# display.net
KiCad netlist of a schematic drawn in EAGLE
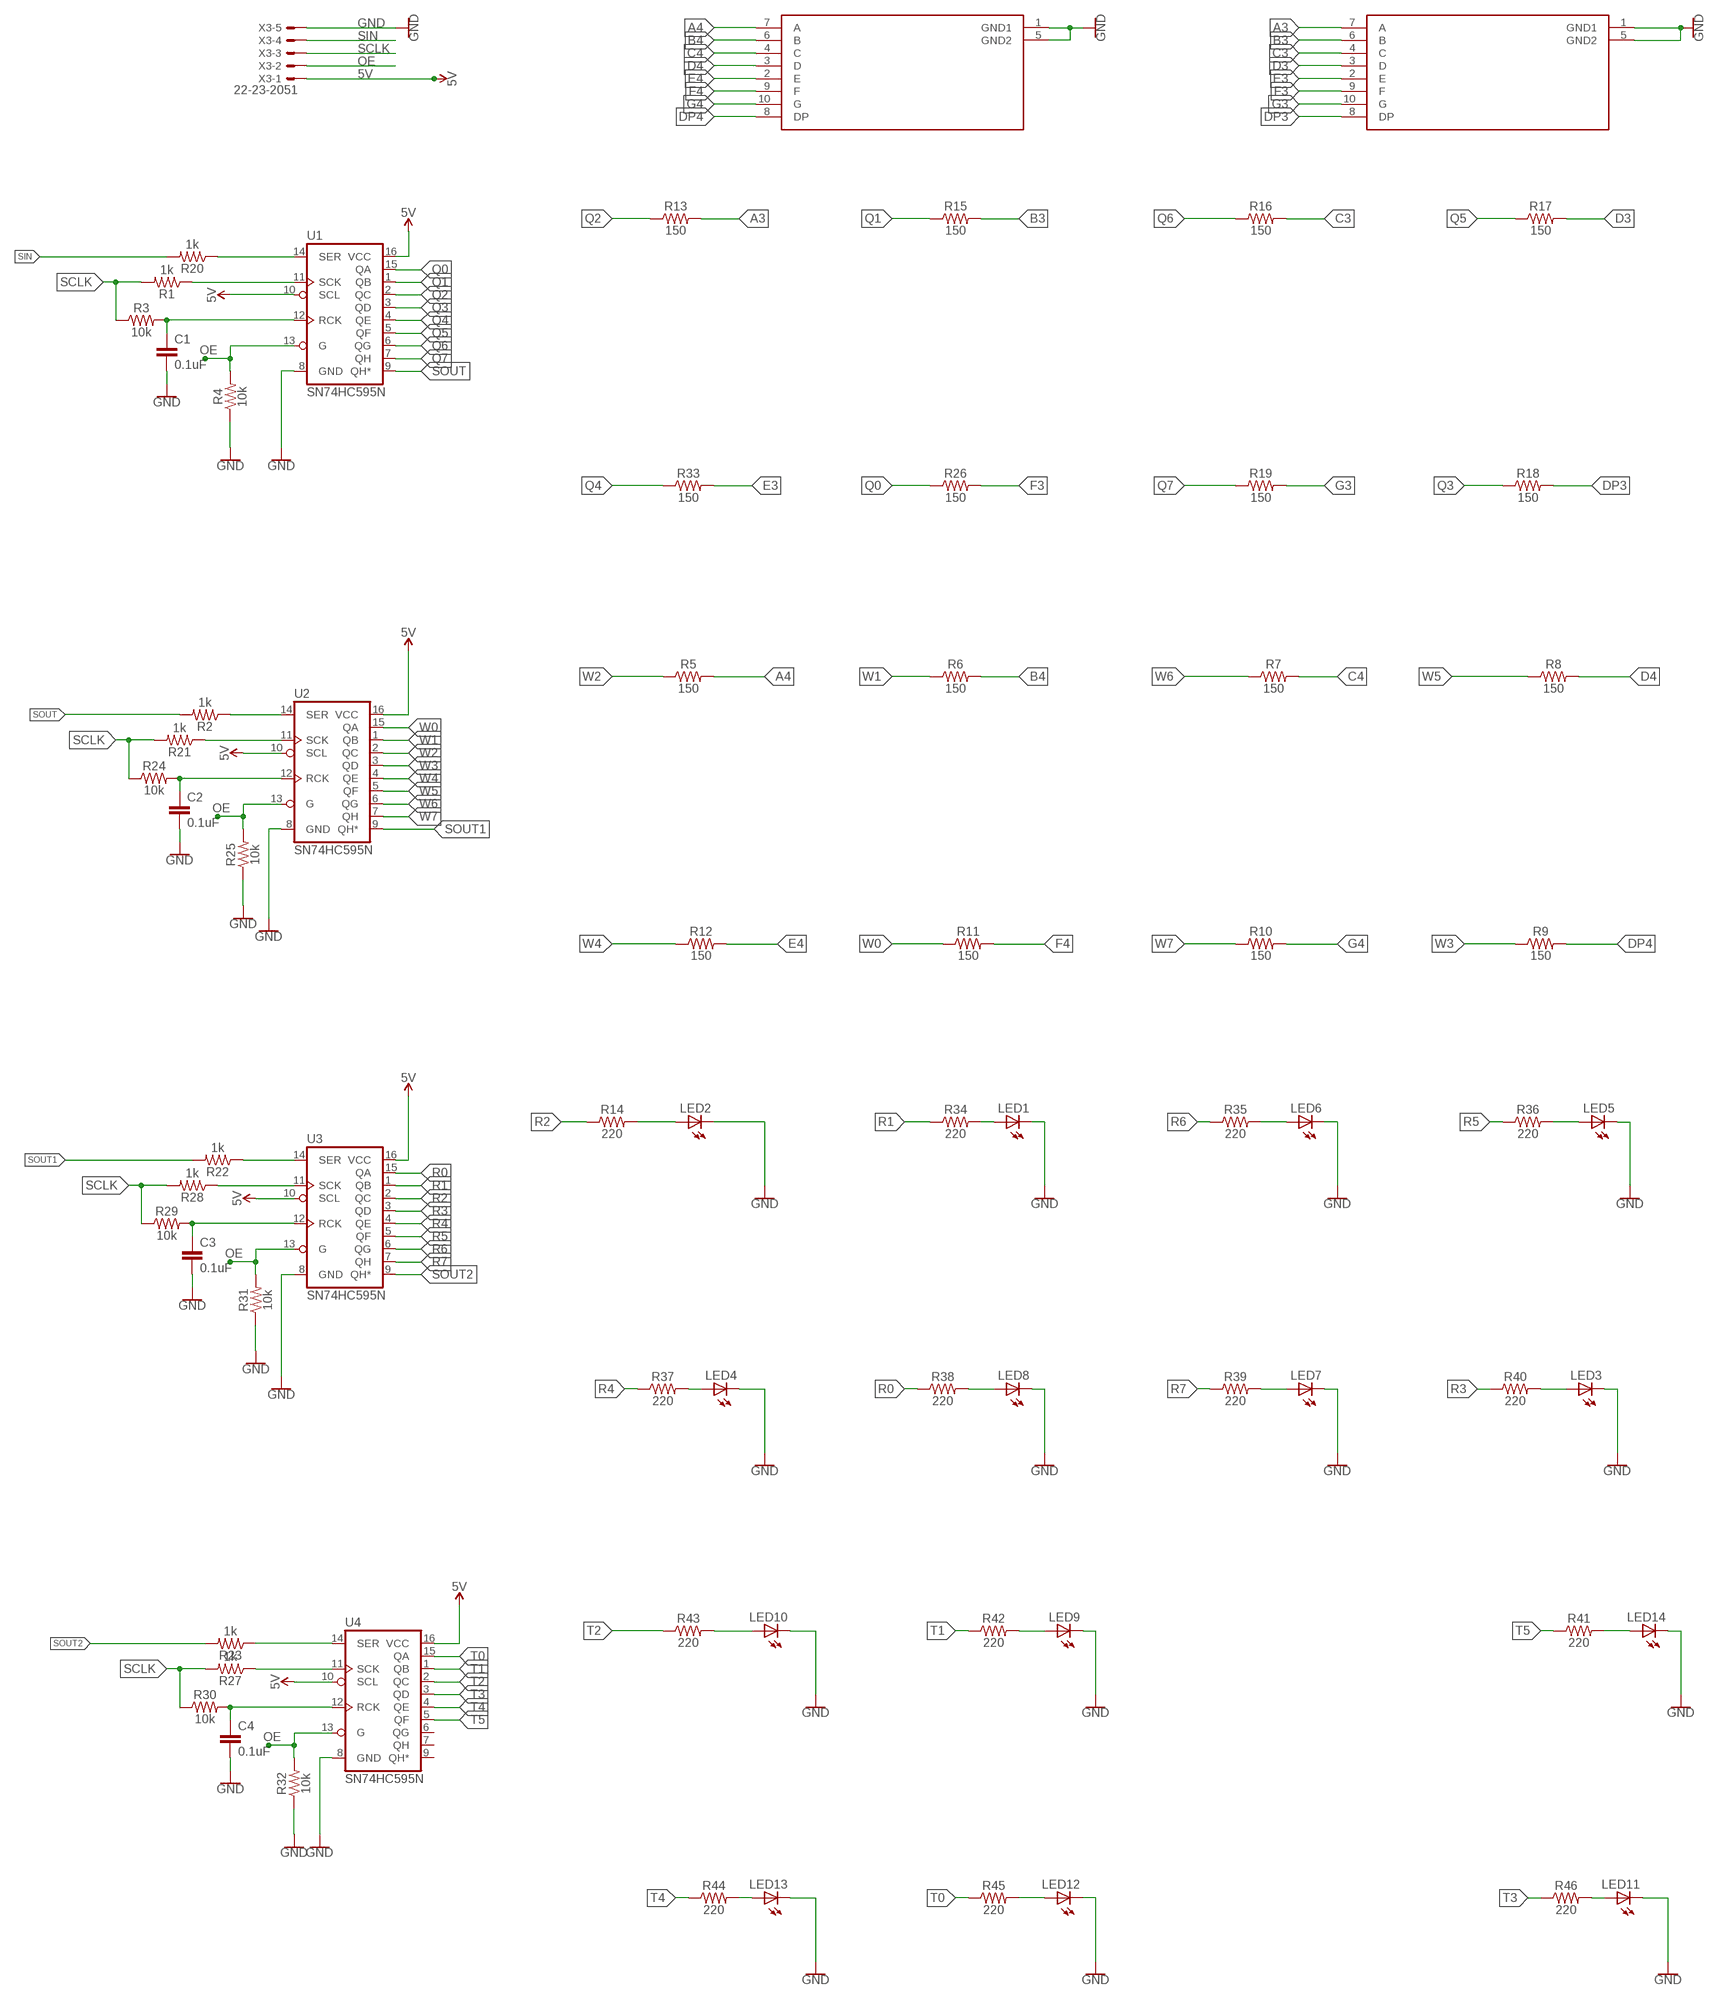
[diagram p0: schematic, sheet 1]

(export (version "E")
  (design (tool "Eeschema 10.0.6"))
  (components
    (comp (ref "C1")
      (value "0.1uF")
      (footprint "eagle-import:CAP-PTH-2.54")
      (libsource (lib "eagle-import") (part "22PF-PTH-2.54MM-200V-5%"))
    )
    (comp (ref "C2")
      (value "0.1uF")
      (footprint "eagle-import:CAP-PTH-2.54")
      (libsource (lib "eagle-import") (part "22PF-PTH-2.54MM-200V-5%"))
    )
    (comp (ref "C3")
      (value "0.1uF")
      (footprint "eagle-import:CAP-PTH-2.54")
      (libsource (lib "eagle-import") (part "22PF-PTH-2.54MM-200V-5%"))
    )
    (comp (ref "C4")
      (value "0.1uF")
      (footprint "eagle-import:CAP-PTH-2.54")
      (libsource (lib "eagle-import") (part "22PF-PTH-2.54MM-200V-5%"))
    )
    (comp (ref "LED1")
      (value "LED5MM")
      (footprint "eagle-import:LED5MM")
      (libsource (lib "eagle-import") (part "LED5MM"))
    )
    (comp (ref "LED2")
      (value "LED5MM")
      (footprint "eagle-import:LED5MM")
      (libsource (lib "eagle-import") (part "LED5MM"))
    )
    (comp (ref "LED3")
      (value "LED5MM")
      (footprint "eagle-import:LED5MM")
      (libsource (lib "eagle-import") (part "LED5MM"))
    )
    (comp (ref "LED4")
      (value "LED5MM")
      (footprint "eagle-import:LED5MM")
      (libsource (lib "eagle-import") (part "LED5MM"))
    )
    (comp (ref "LED5")
      (value "LED5MM")
      (footprint "eagle-import:LED5MM")
      (libsource (lib "eagle-import") (part "LED5MM"))
    )
    (comp (ref "LED6")
      (value "LED5MM")
      (footprint "eagle-import:LED5MM")
      (libsource (lib "eagle-import") (part "LED5MM"))
    )
    (comp (ref "LED7")
      (value "LED5MM")
      (footprint "eagle-import:LED5MM")
      (libsource (lib "eagle-import") (part "LED5MM"))
    )
    (comp (ref "LED8")
      (value "LED5MM")
      (footprint "eagle-import:LED5MM")
      (libsource (lib "eagle-import") (part "LED5MM"))
    )
    (comp (ref "LED9")
      (value "LED5MM")
      (footprint "eagle-import:LED5MM")
      (libsource (lib "eagle-import") (part "LED5MM"))
    )
    (comp (ref "LED10")
      (value "LED5MM")
      (footprint "eagle-import:LED5MM")
      (libsource (lib "eagle-import") (part "LED5MM"))
    )
    (comp (ref "LED11")
      (value "LED5MM")
      (footprint "eagle-import:LED5MM")
      (libsource (lib "eagle-import") (part "LED5MM"))
    )
    (comp (ref "LED12")
      (value "LED5MM")
      (footprint "eagle-import:LED5MM")
      (libsource (lib "eagle-import") (part "LED5MM"))
    )
    (comp (ref "LED13")
      (value "LED5MM")
      (footprint "eagle-import:LED5MM")
      (libsource (lib "eagle-import") (part "LED5MM"))
    )
    (comp (ref "LED14")
      (value "LED5MM")
      (footprint "eagle-import:LED5MM")
      (libsource (lib "eagle-import") (part "LED5MM"))
    )
    (comp (ref "R1")
      (value "1k")
      (footprint "eagle-import:AXIAL-0.3")
      (libsource (lib "eagle-import") (part "1KOHM-HORIZ-1/4W-5%"))
    )
    (comp (ref "R2")
      (value "1k")
      (footprint "eagle-import:AXIAL-0.3")
      (libsource (lib "eagle-import") (part "1KOHM-HORIZ-1/4W-5%"))
    )
    (comp (ref "R3")
      (value "10k")
      (footprint "eagle-import:AXIAL-0.3")
      (libsource (lib "eagle-import") (part "10KOHM-HORIZ-1/4W-5%"))
    )
    (comp (ref "R4")
      (value "10k")
      (footprint "eagle-import:AXIAL-0.3")
      (libsource (lib "eagle-import") (part "10KOHM-HORIZ-1/4W-5%"))
    )
    (comp (ref "R5")
      (value "150")
      (footprint "eagle-import:AXIAL-0.3")
      (libsource (lib "eagle-import") (part "10KOHM-HORIZ-1/4W-5%"))
    )
    (comp (ref "R6")
      (value "150")
      (footprint "eagle-import:AXIAL-0.3")
      (libsource (lib "eagle-import") (part "10KOHM-HORIZ-1/4W-5%"))
    )
    (comp (ref "R7")
      (value "150")
      (footprint "eagle-import:AXIAL-0.3")
      (libsource (lib "eagle-import") (part "10KOHM-HORIZ-1/4W-5%"))
    )
    (comp (ref "R8")
      (value "150")
      (footprint "eagle-import:AXIAL-0.3")
      (libsource (lib "eagle-import") (part "10KOHM-HORIZ-1/4W-5%"))
    )
    (comp (ref "R9")
      (value "150")
      (footprint "eagle-import:AXIAL-0.3")
      (libsource (lib "eagle-import") (part "10KOHM-HORIZ-1/4W-5%"))
    )
    (comp (ref "R10")
      (value "150")
      (footprint "eagle-import:AXIAL-0.3")
      (libsource (lib "eagle-import") (part "10KOHM-HORIZ-1/4W-5%"))
    )
    (comp (ref "R11")
      (value "150")
      (footprint "eagle-import:AXIAL-0.3")
      (libsource (lib "eagle-import") (part "10KOHM-HORIZ-1/4W-5%"))
    )
    (comp (ref "R12")
      (value "150")
      (footprint "eagle-import:AXIAL-0.3")
      (libsource (lib "eagle-import") (part "10KOHM-HORIZ-1/4W-5%"))
    )
    (comp (ref "R13")
      (value "150")
      (footprint "eagle-import:AXIAL-0.3")
      (libsource (lib "eagle-import") (part "10KOHM-HORIZ-1/4W-5%"))
    )
    (comp (ref "R14")
      (value "220")
      (footprint "eagle-import:AXIAL-0.3")
      (libsource (lib "eagle-import") (part "10KOHM-HORIZ-1/4W-5%"))
    )
    (comp (ref "R15")
      (value "150")
      (footprint "eagle-import:AXIAL-0.3")
      (libsource (lib "eagle-import") (part "10KOHM-HORIZ-1/4W-5%"))
    )
    (comp (ref "R16")
      (value "150")
      (footprint "eagle-import:AXIAL-0.3")
      (libsource (lib "eagle-import") (part "10KOHM-HORIZ-1/4W-5%"))
    )
    (comp (ref "R17")
      (value "150")
      (footprint "eagle-import:AXIAL-0.3")
      (libsource (lib "eagle-import") (part "10KOHM-HORIZ-1/4W-5%"))
    )
    (comp (ref "R18")
      (value "150")
      (footprint "eagle-import:AXIAL-0.3")
      (libsource (lib "eagle-import") (part "10KOHM-HORIZ-1/4W-5%"))
    )
    (comp (ref "R19")
      (value "150")
      (footprint "eagle-import:AXIAL-0.3")
      (libsource (lib "eagle-import") (part "10KOHM-HORIZ-1/4W-5%"))
    )
    (comp (ref "R20")
      (value "1k")
      (footprint "eagle-import:AXIAL-0.3")
      (libsource (lib "eagle-import") (part "1KOHM-HORIZ-1/4W-5%"))
    )
    (comp (ref "R21")
      (value "1k")
      (footprint "eagle-import:AXIAL-0.3")
      (libsource (lib "eagle-import") (part "1KOHM-HORIZ-1/4W-5%"))
    )
    (comp (ref "R22")
      (value "1k")
      (footprint "eagle-import:AXIAL-0.3")
      (libsource (lib "eagle-import") (part "1KOHM-HORIZ-1/4W-5%"))
    )
    (comp (ref "R23")
      (value "1k")
      (footprint "eagle-import:AXIAL-0.3")
      (libsource (lib "eagle-import") (part "1KOHM-HORIZ-1/4W-5%"))
    )
    (comp (ref "R24")
      (value "10k")
      (footprint "eagle-import:AXIAL-0.3")
      (libsource (lib "eagle-import") (part "10KOHM-HORIZ-1/4W-5%"))
    )
    (comp (ref "R25")
      (value "10k")
      (footprint "eagle-import:AXIAL-0.3")
      (libsource (lib "eagle-import") (part "10KOHM-HORIZ-1/4W-5%"))
    )
    (comp (ref "R26")
      (value "150")
      (footprint "eagle-import:AXIAL-0.3")
      (libsource (lib "eagle-import") (part "10KOHM-HORIZ-1/4W-5%"))
    )
    (comp (ref "R27")
      (value "1k")
      (footprint "eagle-import:AXIAL-0.3")
      (libsource (lib "eagle-import") (part "1KOHM-HORIZ-1/4W-5%"))
    )
    (comp (ref "R28")
      (value "1k")
      (footprint "eagle-import:AXIAL-0.3")
      (libsource (lib "eagle-import") (part "1KOHM-HORIZ-1/4W-5%"))
    )
    (comp (ref "R29")
      (value "10k")
      (footprint "eagle-import:AXIAL-0.3")
      (libsource (lib "eagle-import") (part "10KOHM-HORIZ-1/4W-5%"))
    )
    (comp (ref "R30")
      (value "10k")
      (footprint "eagle-import:AXIAL-0.3")
      (libsource (lib "eagle-import") (part "10KOHM-HORIZ-1/4W-5%"))
    )
    (comp (ref "R31")
      (value "10k")
      (footprint "eagle-import:AXIAL-0.3")
      (libsource (lib "eagle-import") (part "10KOHM-HORIZ-1/4W-5%"))
    )
    (comp (ref "R32")
      (value "10k")
      (footprint "eagle-import:AXIAL-0.3")
      (libsource (lib "eagle-import") (part "10KOHM-HORIZ-1/4W-5%"))
    )
    (comp (ref "R33")
      (value "150")
      (footprint "eagle-import:AXIAL-0.3")
      (libsource (lib "eagle-import") (part "10KOHM-HORIZ-1/4W-5%"))
    )
    (comp (ref "R34")
      (value "220")
      (footprint "eagle-import:AXIAL-0.3")
      (libsource (lib "eagle-import") (part "10KOHM-HORIZ-1/4W-5%"))
    )
    (comp (ref "R35")
      (value "220")
      (footprint "eagle-import:AXIAL-0.3")
      (libsource (lib "eagle-import") (part "10KOHM-HORIZ-1/4W-5%"))
    )
    (comp (ref "R36")
      (value "220")
      (footprint "eagle-import:AXIAL-0.3")
      (libsource (lib "eagle-import") (part "10KOHM-HORIZ-1/4W-5%"))
    )
    (comp (ref "R37")
      (value "220")
      (footprint "eagle-import:AXIAL-0.3")
      (libsource (lib "eagle-import") (part "10KOHM-HORIZ-1/4W-5%"))
    )
    (comp (ref "R38")
      (value "220")
      (footprint "eagle-import:AXIAL-0.3")
      (libsource (lib "eagle-import") (part "10KOHM-HORIZ-1/4W-5%"))
    )
    (comp (ref "R39")
      (value "220")
      (footprint "eagle-import:AXIAL-0.3")
      (libsource (lib "eagle-import") (part "10KOHM-HORIZ-1/4W-5%"))
    )
    (comp (ref "R40")
      (value "220")
      (footprint "eagle-import:AXIAL-0.3")
      (libsource (lib "eagle-import") (part "10KOHM-HORIZ-1/4W-5%"))
    )
    (comp (ref "R41")
      (value "220")
      (footprint "eagle-import:AXIAL-0.3")
      (libsource (lib "eagle-import") (part "10KOHM-HORIZ-1/4W-5%"))
    )
    (comp (ref "R42")
      (value "220")
      (footprint "eagle-import:AXIAL-0.3")
      (libsource (lib "eagle-import") (part "10KOHM-HORIZ-1/4W-5%"))
    )
    (comp (ref "R43")
      (value "220")
      (footprint "eagle-import:AXIAL-0.3")
      (libsource (lib "eagle-import") (part "10KOHM-HORIZ-1/4W-5%"))
    )
    (comp (ref "R44")
      (value "220")
      (footprint "eagle-import:AXIAL-0.3")
      (libsource (lib "eagle-import") (part "10KOHM-HORIZ-1/4W-5%"))
    )
    (comp (ref "R45")
      (value "220")
      (footprint "eagle-import:AXIAL-0.3")
      (libsource (lib "eagle-import") (part "10KOHM-HORIZ-1/4W-5%"))
    )
    (comp (ref "R46")
      (value "220")
      (footprint "eagle-import:AXIAL-0.3")
      (libsource (lib "eagle-import") (part "10KOHM-HORIZ-1/4W-5%"))
    )
    (comp (ref "U$1")
      (value "DISPLAY1.2")
      (footprint "eagle-import:1.2INCH")
      (libsource (lib "eagle-import") (part "DISPLAY1.2"))
    )
    (comp (ref "U$2")
      (value "DISPLAY1.2")
      (footprint "eagle-import:1.2INCH")
      (libsource (lib "eagle-import") (part "DISPLAY1.2"))
    )
    (comp (ref "U1")
      (value "SN74HC595N")
      (footprint "eagle-import:DIP16")
      (libsource (lib "eagle-import") (part "74595NHC"))
    )
    (comp (ref "U2")
      (value "SN74HC595N")
      (footprint "eagle-import:DIP16")
      (libsource (lib "eagle-import") (part "74595NHC"))
    )
    (comp (ref "U3")
      (value "SN74HC595N")
      (footprint "eagle-import:DIP16")
      (libsource (lib "eagle-import") (part "74595NHC"))
    )
    (comp (ref "U4")
      (value "SN74HC595N")
      (footprint "eagle-import:DIP16")
      (libsource (lib "eagle-import") (part "74595NHC"))
    )
    (comp (ref "X3")
      (value "22-23-2051")
      (footprint "eagle-import:22-23-2051")
      (fields (field (name "MF") "MOLEX"))
      (libsource (lib "eagle-import") (part "22-23-2051"))
    )
  )
  (nets
    (net (code "1") (name "/OE") (class "Default")
      (node (ref "R25") (pin "P$2") (pinfunction "2_P$2") (pintype "passive"))
      (node (ref "R31") (pin "P$2") (pinfunction "2_P$2") (pintype "passive"))
      (node (ref "R32") (pin "P$2") (pinfunction "2_P$2") (pintype "passive"))
      (node (ref "R4") (pin "P$2") (pinfunction "2_P$2") (pintype "passive"))
      (node (ref "U1") (pin "13") (pinfunction "G_13") (pintype "input"))
      (node (ref "U2") (pin "13") (pinfunction "G_13") (pintype "input"))
      (node (ref "U3") (pin "13") (pinfunction "G_13") (pintype "input"))
      (node (ref "U4") (pin "13") (pinfunction "G_13") (pintype "input"))
      (node (ref "X3") (pin "2") (pinfunction "S_2") (pintype "passive"))
    )
    (net (code "2") (name "5V") (class "Default")
      (node (ref "U1") (pin "10") (pinfunction "SCL_10") (pintype "input"))
      (node (ref "U1") (pin "16") (pinfunction "VCC_16") (pintype "power_in"))
      (node (ref "U2") (pin "10") (pinfunction "SCL_10") (pintype "input"))
      (node (ref "U2") (pin "16") (pinfunction "VCC_16") (pintype "power_in"))
      (node (ref "U3") (pin "10") (pinfunction "SCL_10") (pintype "input"))
      (node (ref "U3") (pin "16") (pinfunction "VCC_16") (pintype "power_in"))
      (node (ref "U4") (pin "10") (pinfunction "SCL_10") (pintype "input"))
      (node (ref "U4") (pin "16") (pinfunction "VCC_16") (pintype "power_in"))
      (node (ref "X3") (pin "1") (pinfunction "S_1") (pintype "passive"))
    )
    (net (code "3") (name "A3") (class "Default")
      (node (ref "R13") (pin "P$2") (pinfunction "2_P$2") (pintype "passive"))
      (node (ref "U$1") (pin "7") (pinfunction "A_7") (pintype "bidirectional"))
    )
    (net (code "4") (name "A4") (class "Default")
      (node (ref "R5") (pin "P$2") (pinfunction "2_P$2") (pintype "passive"))
      (node (ref "U$2") (pin "7") (pinfunction "A_7") (pintype "bidirectional"))
    )
    (net (code "5") (name "B3") (class "Default")
      (node (ref "R15") (pin "P$2") (pinfunction "2_P$2") (pintype "passive"))
      (node (ref "U$1") (pin "6") (pinfunction "B_6") (pintype "bidirectional"))
    )
    (net (code "6") (name "B4") (class "Default")
      (node (ref "R6") (pin "P$2") (pinfunction "2_P$2") (pintype "passive"))
      (node (ref "U$2") (pin "6") (pinfunction "B_6") (pintype "bidirectional"))
    )
    (net (code "7") (name "C3") (class "Default")
      (node (ref "R16") (pin "P$2") (pinfunction "2_P$2") (pintype "passive"))
      (node (ref "U$1") (pin "4") (pinfunction "C_4") (pintype "bidirectional"))
    )
    (net (code "8") (name "C4") (class "Default")
      (node (ref "R7") (pin "P$2") (pinfunction "2_P$2") (pintype "passive"))
      (node (ref "U$2") (pin "4") (pinfunction "C_4") (pintype "bidirectional"))
    )
    (net (code "9") (name "D3") (class "Default")
      (node (ref "R17") (pin "P$2") (pinfunction "2_P$2") (pintype "passive"))
      (node (ref "U$1") (pin "3") (pinfunction "D_3") (pintype "bidirectional"))
    )
    (net (code "10") (name "D4") (class "Default")
      (node (ref "R8") (pin "P$2") (pinfunction "2_P$2") (pintype "passive"))
      (node (ref "U$2") (pin "3") (pinfunction "D_3") (pintype "bidirectional"))
    )
    (net (code "11") (name "DP3") (class "Default")
      (node (ref "R18") (pin "P$2") (pinfunction "2_P$2") (pintype "passive"))
      (node (ref "U$1") (pin "8") (pinfunction "DP_8") (pintype "bidirectional"))
    )
    (net (code "12") (name "DP4") (class "Default")
      (node (ref "R9") (pin "P$2") (pinfunction "2_P$2") (pintype "passive"))
      (node (ref "U$2") (pin "8") (pinfunction "DP_8") (pintype "bidirectional"))
    )
    (net (code "13") (name "E3") (class "Default")
      (node (ref "R33") (pin "P$2") (pinfunction "2_P$2") (pintype "passive"))
      (node (ref "U$1") (pin "2") (pinfunction "E_2") (pintype "bidirectional"))
    )
    (net (code "14") (name "E4") (class "Default")
      (node (ref "R12") (pin "P$2") (pinfunction "2_P$2") (pintype "passive"))
      (node (ref "U$2") (pin "2") (pinfunction "E_2") (pintype "bidirectional"))
    )
    (net (code "15") (name "F3") (class "Default")
      (node (ref "R26") (pin "P$2") (pinfunction "2_P$2") (pintype "passive"))
      (node (ref "U$1") (pin "9") (pinfunction "F_9") (pintype "bidirectional"))
    )
    (net (code "16") (name "F4") (class "Default")
      (node (ref "R11") (pin "P$2") (pinfunction "2_P$2") (pintype "passive"))
      (node (ref "U$2") (pin "9") (pinfunction "F_9") (pintype "bidirectional"))
    )
    (net (code "17") (name "G3") (class "Default")
      (node (ref "R19") (pin "P$2") (pinfunction "2_P$2") (pintype "passive"))
      (node (ref "U$1") (pin "10") (pinfunction "G_10") (pintype "bidirectional"))
    )
    (net (code "18") (name "G4") (class "Default")
      (node (ref "R10") (pin "P$2") (pinfunction "2_P$2") (pintype "passive"))
      (node (ref "U$2") (pin "10") (pinfunction "G_10") (pintype "bidirectional"))
    )
    (net (code "19") (name "GND") (class "Default")
      (node (ref "C1") (pin "2") (pinfunction "2_2") (pintype "passive"))
      (node (ref "C2") (pin "2") (pinfunction "2_2") (pintype "passive"))
      (node (ref "C3") (pin "2") (pinfunction "2_2") (pintype "passive"))
      (node (ref "C4") (pin "2") (pinfunction "2_2") (pintype "passive"))
      (node (ref "LED1") (pin "K") (pinfunction "C_K") (pintype "passive"))
      (node (ref "LED10") (pin "K") (pinfunction "C_K") (pintype "passive"))
      (node (ref "LED11") (pin "K") (pinfunction "C_K") (pintype "passive"))
      (node (ref "LED12") (pin "K") (pinfunction "C_K") (pintype "passive"))
      (node (ref "LED13") (pin "K") (pinfunction "C_K") (pintype "passive"))
      (node (ref "LED14") (pin "K") (pinfunction "C_K") (pintype "passive"))
      (node (ref "LED2") (pin "K") (pinfunction "C_K") (pintype "passive"))
      (node (ref "LED3") (pin "K") (pinfunction "C_K") (pintype "passive"))
      (node (ref "LED4") (pin "K") (pinfunction "C_K") (pintype "passive"))
      (node (ref "LED5") (pin "K") (pinfunction "C_K") (pintype "passive"))
      (node (ref "LED6") (pin "K") (pinfunction "C_K") (pintype "passive"))
      (node (ref "LED7") (pin "K") (pinfunction "C_K") (pintype "passive"))
      (node (ref "LED8") (pin "K") (pinfunction "C_K") (pintype "passive"))
      (node (ref "LED9") (pin "K") (pinfunction "C_K") (pintype "passive"))
      (node (ref "R25") (pin "P$1") (pinfunction "1_P$1") (pintype "passive"))
      (node (ref "R31") (pin "P$1") (pinfunction "1_P$1") (pintype "passive"))
      (node (ref "R32") (pin "P$1") (pinfunction "1_P$1") (pintype "passive"))
      (node (ref "R4") (pin "P$1") (pinfunction "1_P$1") (pintype "passive"))
      (node (ref "U$1") (pin "1") (pinfunction "GND1_1") (pintype "bidirectional"))
      (node (ref "U$1") (pin "5") (pinfunction "GND2_5") (pintype "bidirectional"))
      (node (ref "U$2") (pin "1") (pinfunction "GND1_1") (pintype "bidirectional"))
      (node (ref "U$2") (pin "5") (pinfunction "GND2_5") (pintype "bidirectional"))
      (node (ref "U1") (pin "8") (pinfunction "GND_8") (pintype "power_in"))
      (node (ref "U2") (pin "8") (pinfunction "GND_8") (pintype "power_in"))
      (node (ref "U3") (pin "8") (pinfunction "GND_8") (pintype "power_in"))
      (node (ref "U4") (pin "8") (pinfunction "GND_8") (pintype "power_in"))
      (node (ref "X3") (pin "5") (pinfunction "S_5") (pintype "passive"))
    )
    (net (code "20") (name "Net-(R1-1)") (class "Default")
      (node (ref "R1") (pin "P$1") (pinfunction "1_P$1") (pintype "passive"))
      (node (ref "U1") (pin "11") (pinfunction "SCK_11") (pintype "input"))
    )
    (net (code "21") (name "Net-(R2-1)") (class "Default")
      (node (ref "R2") (pin "P$1") (pinfunction "1_P$1") (pintype "passive"))
      (node (ref "U2") (pin "14") (pinfunction "SER_14") (pintype "input"))
    )
    (net (code "22") (name "Net-(R3-2)") (class "Default")
      (node (ref "C1") (pin "1") (pinfunction "1_1") (pintype "passive"))
      (node (ref "R3") (pin "P$2") (pinfunction "2_P$2") (pintype "passive"))
      (node (ref "U1") (pin "12") (pinfunction "RCK_12") (pintype "input"))
    )
    (net (code "23") (name "Net-(R14-2)") (class "Default")
      (node (ref "LED2") (pin "A") (pinfunction "A_A") (pintype "passive"))
      (node (ref "R14") (pin "P$2") (pinfunction "2_P$2") (pintype "passive"))
    )
    (net (code "24") (name "Net-(R20-1)") (class "Default")
      (node (ref "R20") (pin "P$1") (pinfunction "1_P$1") (pintype "passive"))
      (node (ref "U1") (pin "14") (pinfunction "SER_14") (pintype "input"))
    )
    (net (code "25") (name "Net-(R21-1)") (class "Default")
      (node (ref "R21") (pin "P$1") (pinfunction "1_P$1") (pintype "passive"))
      (node (ref "U2") (pin "11") (pinfunction "SCK_11") (pintype "input"))
    )
    (net (code "26") (name "Net-(R22-1)") (class "Default")
      (node (ref "R22") (pin "P$1") (pinfunction "1_P$1") (pintype "passive"))
      (node (ref "U3") (pin "14") (pinfunction "SER_14") (pintype "input"))
    )
    (net (code "27") (name "Net-(R23-1)") (class "Default")
      (node (ref "R23") (pin "P$1") (pinfunction "1_P$1") (pintype "passive"))
      (node (ref "U4") (pin "14") (pinfunction "SER_14") (pintype "input"))
    )
    (net (code "28") (name "Net-(R24-2)") (class "Default")
      (node (ref "C2") (pin "1") (pinfunction "1_1") (pintype "passive"))
      (node (ref "R24") (pin "P$2") (pinfunction "2_P$2") (pintype "passive"))
      (node (ref "U2") (pin "12") (pinfunction "RCK_12") (pintype "input"))
    )
    (net (code "29") (name "Net-(R27-1)") (class "Default")
      (node (ref "R27") (pin "P$1") (pinfunction "1_P$1") (pintype "passive"))
      (node (ref "U4") (pin "11") (pinfunction "SCK_11") (pintype "input"))
    )
    (net (code "30") (name "Net-(R28-1)") (class "Default")
      (node (ref "R28") (pin "P$1") (pinfunction "1_P$1") (pintype "passive"))
      (node (ref "U3") (pin "11") (pinfunction "SCK_11") (pintype "input"))
    )
    (net (code "31") (name "Net-(R29-2)") (class "Default")
      (node (ref "C3") (pin "1") (pinfunction "1_1") (pintype "passive"))
      (node (ref "R29") (pin "P$2") (pinfunction "2_P$2") (pintype "passive"))
      (node (ref "U3") (pin "12") (pinfunction "RCK_12") (pintype "input"))
    )
    (net (code "32") (name "Net-(R30-2)") (class "Default")
      (node (ref "C4") (pin "1") (pinfunction "1_1") (pintype "passive"))
      (node (ref "R30") (pin "P$2") (pinfunction "2_P$2") (pintype "passive"))
      (node (ref "U4") (pin "12") (pinfunction "RCK_12") (pintype "input"))
    )
    (net (code "33") (name "Net-(R34-2)") (class "Default")
      (node (ref "LED1") (pin "A") (pinfunction "A_A") (pintype "passive"))
      (node (ref "R34") (pin "P$2") (pinfunction "2_P$2") (pintype "passive"))
    )
    (net (code "34") (name "Net-(R35-2)") (class "Default")
      (node (ref "LED6") (pin "A") (pinfunction "A_A") (pintype "passive"))
      (node (ref "R35") (pin "P$2") (pinfunction "2_P$2") (pintype "passive"))
    )
    (net (code "35") (name "Net-(R36-2)") (class "Default")
      (node (ref "LED5") (pin "A") (pinfunction "A_A") (pintype "passive"))
      (node (ref "R36") (pin "P$2") (pinfunction "2_P$2") (pintype "passive"))
    )
    (net (code "36") (name "Net-(R37-2)") (class "Default")
      (node (ref "LED4") (pin "A") (pinfunction "A_A") (pintype "passive"))
      (node (ref "R37") (pin "P$2") (pinfunction "2_P$2") (pintype "passive"))
    )
    (net (code "37") (name "Net-(R38-2)") (class "Default")
      (node (ref "LED8") (pin "A") (pinfunction "A_A") (pintype "passive"))
      (node (ref "R38") (pin "P$2") (pinfunction "2_P$2") (pintype "passive"))
    )
    (net (code "38") (name "Net-(R39-2)") (class "Default")
      (node (ref "LED7") (pin "A") (pinfunction "A_A") (pintype "passive"))
      (node (ref "R39") (pin "P$2") (pinfunction "2_P$2") (pintype "passive"))
    )
    (net (code "39") (name "Net-(R40-2)") (class "Default")
      (node (ref "LED3") (pin "A") (pinfunction "A_A") (pintype "passive"))
      (node (ref "R40") (pin "P$2") (pinfunction "2_P$2") (pintype "passive"))
    )
    (net (code "40") (name "Net-(R41-2)") (class "Default")
      (node (ref "LED14") (pin "A") (pinfunction "A_A") (pintype "passive"))
      (node (ref "R41") (pin "P$2") (pinfunction "2_P$2") (pintype "passive"))
    )
    (net (code "41") (name "Net-(R42-2)") (class "Default")
      (node (ref "LED9") (pin "A") (pinfunction "A_A") (pintype "passive"))
      (node (ref "R42") (pin "P$2") (pinfunction "2_P$2") (pintype "passive"))
    )
    (net (code "42") (name "Net-(R43-2)") (class "Default")
      (node (ref "LED10") (pin "A") (pinfunction "A_A") (pintype "passive"))
      (node (ref "R43") (pin "P$2") (pinfunction "2_P$2") (pintype "passive"))
    )
    (net (code "43") (name "Net-(R44-2)") (class "Default")
      (node (ref "LED13") (pin "A") (pinfunction "A_A") (pintype "passive"))
      (node (ref "R44") (pin "P$2") (pinfunction "2_P$2") (pintype "passive"))
    )
    (net (code "44") (name "Net-(R45-2)") (class "Default")
      (node (ref "LED12") (pin "A") (pinfunction "A_A") (pintype "passive"))
      (node (ref "R45") (pin "P$2") (pinfunction "2_P$2") (pintype "passive"))
    )
    (net (code "45") (name "Net-(R46-2)") (class "Default")
      (node (ref "LED11") (pin "A") (pinfunction "A_A") (pintype "passive"))
      (node (ref "R46") (pin "P$2") (pinfunction "2_P$2") (pintype "passive"))
    )
    (net (code "46") (name "Q0") (class "Default")
      (node (ref "R26") (pin "P$1") (pinfunction "1_P$1") (pintype "passive"))
      (node (ref "U1") (pin "15") (pinfunction "QA_15") (pintype "tri_state"))
    )
    (net (code "47") (name "Q1") (class "Default")
      (node (ref "R15") (pin "P$1") (pinfunction "1_P$1") (pintype "passive"))
      (node (ref "U1") (pin "1") (pinfunction "QB_1") (pintype "tri_state"))
    )
    (net (code "48") (name "Q2") (class "Default")
      (node (ref "R13") (pin "P$1") (pinfunction "1_P$1") (pintype "passive"))
      (node (ref "U1") (pin "2") (pinfunction "QC_2") (pintype "tri_state"))
    )
    (net (code "49") (name "Q3") (class "Default")
      (node (ref "R18") (pin "P$1") (pinfunction "1_P$1") (pintype "passive"))
      (node (ref "U1") (pin "3") (pinfunction "QD_3") (pintype "tri_state"))
    )
    (net (code "50") (name "Q4") (class "Default")
      (node (ref "R33") (pin "P$1") (pinfunction "1_P$1") (pintype "passive"))
      (node (ref "U1") (pin "4") (pinfunction "QE_4") (pintype "tri_state"))
    )
    (net (code "51") (name "Q5") (class "Default")
      (node (ref "R17") (pin "P$1") (pinfunction "1_P$1") (pintype "passive"))
      (node (ref "U1") (pin "5") (pinfunction "QF_5") (pintype "tri_state"))
    )
    (net (code "52") (name "Q6") (class "Default")
      (node (ref "R16") (pin "P$1") (pinfunction "1_P$1") (pintype "passive"))
      (node (ref "U1") (pin "6") (pinfunction "QG_6") (pintype "tri_state"))
    )
    (net (code "53") (name "Q7") (class "Default")
      (node (ref "R19") (pin "P$1") (pinfunction "1_P$1") (pintype "passive"))
      (node (ref "U1") (pin "7") (pinfunction "QH_7") (pintype "tri_state"))
    )
    (net (code "54") (name "R0") (class "Default")
      (node (ref "R38") (pin "P$1") (pinfunction "1_P$1") (pintype "passive"))
      (node (ref "U3") (pin "15") (pinfunction "QA_15") (pintype "tri_state"))
    )
    (net (code "55") (name "R1") (class "Default")
      (node (ref "R34") (pin "P$1") (pinfunction "1_P$1") (pintype "passive"))
      (node (ref "U3") (pin "1") (pinfunction "QB_1") (pintype "tri_state"))
    )
    (net (code "56") (name "R2") (class "Default")
      (node (ref "R14") (pin "P$1") (pinfunction "1_P$1") (pintype "passive"))
      (node (ref "U3") (pin "2") (pinfunction "QC_2") (pintype "tri_state"))
    )
    (net (code "57") (name "R3") (class "Default")
      (node (ref "R40") (pin "P$1") (pinfunction "1_P$1") (pintype "passive"))
      (node (ref "U3") (pin "3") (pinfunction "QD_3") (pintype "tri_state"))
    )
    (net (code "58") (name "R4") (class "Default")
      (node (ref "R37") (pin "P$1") (pinfunction "1_P$1") (pintype "passive"))
      (node (ref "U3") (pin "4") (pinfunction "QE_4") (pintype "tri_state"))
    )
    (net (code "59") (name "R5") (class "Default")
      (node (ref "R36") (pin "P$1") (pinfunction "1_P$1") (pintype "passive"))
      (node (ref "U3") (pin "5") (pinfunction "QF_5") (pintype "tri_state"))
    )
    (net (code "60") (name "R6") (class "Default")
      (node (ref "R35") (pin "P$1") (pinfunction "1_P$1") (pintype "passive"))
      (node (ref "U3") (pin "6") (pinfunction "QG_6") (pintype "tri_state"))
    )
    (net (code "61") (name "R7") (class "Default")
      (node (ref "R39") (pin "P$1") (pinfunction "1_P$1") (pintype "passive"))
      (node (ref "U3") (pin "7") (pinfunction "QH_7") (pintype "tri_state"))
    )
    (net (code "62") (name "SCLK") (class "Default")
      (node (ref "R1") (pin "P$2") (pinfunction "2_P$2") (pintype "passive"))
      (node (ref "R21") (pin "P$2") (pinfunction "2_P$2") (pintype "passive"))
      (node (ref "R24") (pin "P$1") (pinfunction "1_P$1") (pintype "passive"))
      (node (ref "R27") (pin "P$2") (pinfunction "2_P$2") (pintype "passive"))
      (node (ref "R28") (pin "P$2") (pinfunction "2_P$2") (pintype "passive"))
      (node (ref "R29") (pin "P$1") (pinfunction "1_P$1") (pintype "passive"))
      (node (ref "R3") (pin "P$1") (pinfunction "1_P$1") (pintype "passive"))
      (node (ref "R30") (pin "P$1") (pinfunction "1_P$1") (pintype "passive"))
      (node (ref "X3") (pin "3") (pinfunction "S_3") (pintype "passive"))
    )
    (net (code "63") (name "SIN") (class "Default")
      (node (ref "R20") (pin "P$2") (pinfunction "2_P$2") (pintype "passive"))
      (node (ref "X3") (pin "4") (pinfunction "S_4") (pintype "passive"))
    )
    (net (code "64") (name "SOUT") (class "Default")
      (node (ref "R2") (pin "P$2") (pinfunction "2_P$2") (pintype "passive"))
      (node (ref "U1") (pin "9") (pinfunction "QH*_9") (pintype "tri_state"))
    )
    (net (code "65") (name "SOUT1") (class "Default")
      (node (ref "R22") (pin "P$2") (pinfunction "2_P$2") (pintype "passive"))
      (node (ref "U2") (pin "9") (pinfunction "QH*_9") (pintype "tri_state"))
    )
    (net (code "66") (name "SOUT2") (class "Default")
      (node (ref "R23") (pin "P$2") (pinfunction "2_P$2") (pintype "passive"))
      (node (ref "U3") (pin "9") (pinfunction "QH*_9") (pintype "tri_state"))
    )
    (net (code "67") (name "T0") (class "Default")
      (node (ref "R45") (pin "P$1") (pinfunction "1_P$1") (pintype "passive"))
      (node (ref "U4") (pin "15") (pinfunction "QA_15") (pintype "tri_state"))
    )
    (net (code "68") (name "T1") (class "Default")
      (node (ref "R42") (pin "P$1") (pinfunction "1_P$1") (pintype "passive"))
      (node (ref "U4") (pin "1") (pinfunction "QB_1") (pintype "tri_state"))
    )
    (net (code "69") (name "T2") (class "Default")
      (node (ref "R43") (pin "P$1") (pinfunction "1_P$1") (pintype "passive"))
      (node (ref "U4") (pin "2") (pinfunction "QC_2") (pintype "tri_state"))
    )
    (net (code "70") (name "T3") (class "Default")
      (node (ref "R46") (pin "P$1") (pinfunction "1_P$1") (pintype "passive"))
      (node (ref "U4") (pin "3") (pinfunction "QD_3") (pintype "tri_state"))
    )
    (net (code "71") (name "T4") (class "Default")
      (node (ref "R44") (pin "P$1") (pinfunction "1_P$1") (pintype "passive"))
      (node (ref "U4") (pin "4") (pinfunction "QE_4") (pintype "tri_state"))
    )
    (net (code "72") (name "T5") (class "Default")
      (node (ref "R41") (pin "P$1") (pinfunction "1_P$1") (pintype "passive"))
      (node (ref "U4") (pin "5") (pinfunction "QF_5") (pintype "tri_state"))
    )
    (net (code "73") (name "W0") (class "Default")
      (node (ref "R11") (pin "P$1") (pinfunction "1_P$1") (pintype "passive"))
      (node (ref "U2") (pin "15") (pinfunction "QA_15") (pintype "tri_state"))
    )
    (net (code "74") (name "W1") (class "Default")
      (node (ref "R6") (pin "P$1") (pinfunction "1_P$1") (pintype "passive"))
      (node (ref "U2") (pin "1") (pinfunction "QB_1") (pintype "tri_state"))
    )
    (net (code "75") (name "W2") (class "Default")
      (node (ref "R5") (pin "P$1") (pinfunction "1_P$1") (pintype "passive"))
      (node (ref "U2") (pin "2") (pinfunction "QC_2") (pintype "tri_state"))
    )
    (net (code "76") (name "W3") (class "Default")
      (node (ref "R9") (pin "P$1") (pinfunction "1_P$1") (pintype "passive"))
      (node (ref "U2") (pin "3") (pinfunction "QD_3") (pintype "tri_state"))
    )
    (net (code "77") (name "W4") (class "Default")
      (node (ref "R12") (pin "P$1") (pinfunction "1_P$1") (pintype "passive"))
      (node (ref "U2") (pin "4") (pinfunction "QE_4") (pintype "tri_state"))
    )
    (net (code "78") (name "W5") (class "Default")
      (node (ref "R8") (pin "P$1") (pinfunction "1_P$1") (pintype "passive"))
      (node (ref "U2") (pin "5") (pinfunction "QF_5") (pintype "tri_state"))
    )
    (net (code "79") (name "W6") (class "Default")
      (node (ref "R7") (pin "P$1") (pinfunction "1_P$1") (pintype "passive"))
      (node (ref "U2") (pin "6") (pinfunction "QG_6") (pintype "tri_state"))
    )
    (net (code "80") (name "W7") (class "Default")
      (node (ref "R10") (pin "P$1") (pinfunction "1_P$1") (pintype "passive"))
      (node (ref "U2") (pin "7") (pinfunction "QH_7") (pintype "tri_state"))
    )
    (net (code "81") (name "unconnected-(U4-QG-Pad6)") (class "Default")
      (node (ref "U4") (pin "6") (pinfunction "QG_6") (pintype "tri_state"))
    )
    (net (code "82") (name "unconnected-(U4-QH*-Pad9)") (class "Default")
      (node (ref "U4") (pin "9") (pinfunction "QH*_9") (pintype "tri_state"))
    )
    (net (code "83") (name "unconnected-(U4-QH-Pad7)") (class "Default")
      (node (ref "U4") (pin "7") (pinfunction "QH_7") (pintype "tri_state"))
    )
  )
)
